# d32.net
KiCad netlist of a schematic drawn in EAGLE
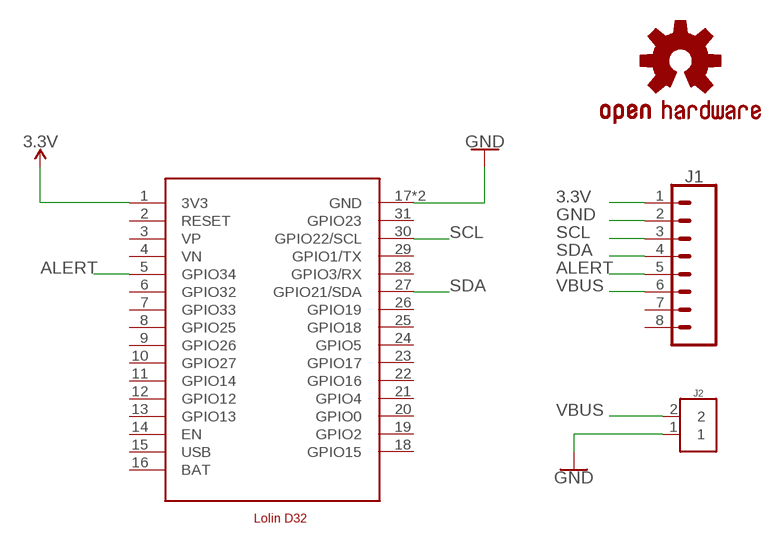
[diagram p0: schematic, sheet 1]

(export (version "E")
  (design (tool "Eeschema 10.0.6"))
  (components
    (comp (ref "J1")
      (value "CONN_08NO_SILK_FEMALE_PTH")
      (footprint "eagle-import:1X08_NO_SILK")
      (libsource (lib "eagle-import") (part "CONN_08NO_SILK_FEMALE_PTH"))
    )
    (comp (ref "J2")
      (value "282834-2")
      (footprint "eagle-import:CONN_282834-2")
      (fields (field (name "MF") "TE Connectivity"))
      (libsource (lib "eagle-import") (part "282834-2"))
    )
    (comp (ref "LOGO1")
      (value "OSHW-LOGOS")
      (footprint "eagle-import:OSHW-LOGO-S")
      (libsource (lib "eagle-import") (part "OSHW-LOGOS"))
    )
    (comp (ref "U1")
      (value "LOLIND32")
      (footprint "eagle-import:LOLIND32")
      (libsource (lib "eagle-import") (part "LOLIND32"))
    )
  )
  (nets
    (net (code "1") (name "/ALERT") (class "Default")
      (node (ref "J1") (pin "5") (pinfunction "5_5") (pintype "passive"))
      (node (ref "U1") (pin "5") (pinfunction "GPIO34_5") (pintype "input"))
    )
    (net (code "2") (name "/BAT") (class "Default")
      (node (ref "U1") (pin "16") (pinfunction "BAT_16") (pintype "power_in"))
    )
    (net (code "3") (name "/SCL") (class "Default")
      (node (ref "J1") (pin "3") (pinfunction "3_3") (pintype "passive"))
      (node (ref "U1") (pin "30") (pinfunction "GPIO22/SCL_30") (pintype "bidirectional"))
    )
    (net (code "4") (name "/SDA") (class "Default")
      (node (ref "J1") (pin "4") (pinfunction "4_4") (pintype "passive"))
      (node (ref "U1") (pin "27") (pinfunction "GPIO21/SDA_27") (pintype "bidirectional"))
    )
    (net (code "5") (name "/USB") (class "Default")
      (node (ref "U1") (pin "15") (pinfunction "USB_15") (pintype "power_in"))
    )
    (net (code "6") (name "/VBUS") (class "Default")
      (node (ref "J1") (pin "6") (pinfunction "6_6") (pintype "passive"))
      (node (ref "J2") (pin "2") (pinfunction "2_2") (pintype "passive"))
    )
    (net (code "7") (name "3.3V") (class "Default")
      (node (ref "J1") (pin "1") (pinfunction "1_1") (pintype "passive"))
      (node (ref "U1") (pin "1") (pinfunction "3V3_1") (pintype "power_in"))
    )
    (net (code "8") (name "GND") (class "Default")
      (node (ref "J1") (pin "2") (pinfunction "2_2") (pintype "passive"))
      (node (ref "J2") (pin "1") (pinfunction "1_1") (pintype "passive"))
      (node (ref "U1") (pin "17") (pinfunction "GND_17") (pintype "power_in"))
      (node (ref "U1") (pin "32") (pinfunction "GND_32") (pintype "power_in"))
    )
    (net (code "9") (name "unconnected-(J1-Pad7)") (class "Default")
      (node (ref "J1") (pin "7") (pinfunction "7_7") (pintype "passive"))
    )
    (net (code "10") (name "unconnected-(J1-Pad8)") (class "Default")
      (node (ref "J1") (pin "8") (pinfunction "8_8") (pintype "passive"))
    )
    (net (code "11") (name "unconnected-(U1-EN-Pad14)") (class "Default")
      (node (ref "U1") (pin "14") (pinfunction "EN_14") (pintype "input"))
    )
    (net (code "12") (name "unconnected-(U1-GPIO0-Pad20)") (class "Default")
      (node (ref "U1") (pin "20") (pinfunction "GPIO0_20") (pintype "bidirectional"))
    )
    (net (code "13") (name "unconnected-(U1-GPIO1{slash}TX-Pad29)") (class "Default")
      (node (ref "U1") (pin "29") (pinfunction "GPIO1/TX_29") (pintype "bidirectional"))
    )
    (net (code "14") (name "unconnected-(U1-GPIO2-Pad19)") (class "Default")
      (node (ref "U1") (pin "19") (pinfunction "GPIO2_19") (pintype "bidirectional"))
    )
    (net (code "15") (name "unconnected-(U1-GPIO3{slash}RX-Pad28)") (class "Default")
      (node (ref "U1") (pin "28") (pinfunction "GPIO3/RX_28") (pintype "bidirectional"))
    )
    (net (code "16") (name "unconnected-(U1-GPIO4-Pad21)") (class "Default")
      (node (ref "U1") (pin "21") (pinfunction "GPIO4_21") (pintype "bidirectional"))
    )
    (net (code "17") (name "unconnected-(U1-GPIO5-Pad24)") (class "Default")
      (node (ref "U1") (pin "24") (pinfunction "GPIO5_24") (pintype "bidirectional"))
    )
    (net (code "18") (name "unconnected-(U1-GPIO12-Pad12)") (class "Default")
      (node (ref "U1") (pin "12") (pinfunction "GPIO12_12") (pintype "bidirectional"))
    )
    (net (code "19") (name "unconnected-(U1-GPIO13-Pad13)") (class "Default")
      (node (ref "U1") (pin "13") (pinfunction "GPIO13_13") (pintype "bidirectional"))
    )
    (net (code "20") (name "unconnected-(U1-GPIO14-Pad11)") (class "Default")
      (node (ref "U1") (pin "11") (pinfunction "GPIO14_11") (pintype "bidirectional"))
    )
    (net (code "21") (name "unconnected-(U1-GPIO15-Pad18)") (class "Default")
      (node (ref "U1") (pin "18") (pinfunction "GPIO15_18") (pintype "bidirectional"))
    )
    (net (code "22") (name "unconnected-(U1-GPIO16-Pad22)") (class "Default")
      (node (ref "U1") (pin "22") (pinfunction "GPIO16_22") (pintype "bidirectional"))
    )
    (net (code "23") (name "unconnected-(U1-GPIO17-Pad23)") (class "Default")
      (node (ref "U1") (pin "23") (pinfunction "GPIO17_23") (pintype "bidirectional"))
    )
    (net (code "24") (name "unconnected-(U1-GPIO18-Pad25)") (class "Default")
      (node (ref "U1") (pin "25") (pinfunction "GPIO18_25") (pintype "bidirectional"))
    )
    (net (code "25") (name "unconnected-(U1-GPIO19-Pad26)") (class "Default")
      (node (ref "U1") (pin "26") (pinfunction "GPIO19_26") (pintype "bidirectional"))
    )
    (net (code "26") (name "unconnected-(U1-GPIO23-Pad31)") (class "Default")
      (node (ref "U1") (pin "31") (pinfunction "GPIO23_31") (pintype "bidirectional"))
    )
    (net (code "27") (name "unconnected-(U1-GPIO25-Pad8)") (class "Default")
      (node (ref "U1") (pin "8") (pinfunction "GPIO25_8") (pintype "bidirectional"))
    )
    (net (code "28") (name "unconnected-(U1-GPIO26-Pad9)") (class "Default")
      (node (ref "U1") (pin "9") (pinfunction "GPIO26_9") (pintype "bidirectional"))
    )
    (net (code "29") (name "unconnected-(U1-GPIO27-Pad10)") (class "Default")
      (node (ref "U1") (pin "10") (pinfunction "GPIO27_10") (pintype "bidirectional"))
    )
    (net (code "30") (name "unconnected-(U1-GPIO32-Pad6)") (class "Default")
      (node (ref "U1") (pin "6") (pinfunction "GPIO32_6") (pintype "bidirectional"))
    )
    (net (code "31") (name "unconnected-(U1-GPIO33-Pad7)") (class "Default")
      (node (ref "U1") (pin "7") (pinfunction "GPIO33_7") (pintype "bidirectional"))
    )
    (net (code "32") (name "unconnected-(U1-RESET-Pad2)") (class "Default")
      (node (ref "U1") (pin "2") (pinfunction "RESET_2") (pintype "input"))
    )
    (net (code "33") (name "unconnected-(U1-VN-Pad4)") (class "Default")
      (node (ref "U1") (pin "4") (pinfunction "VN_4") (pintype "no_connect"))
    )
    (net (code "34") (name "unconnected-(U1-VP-Pad3)") (class "Default")
      (node (ref "U1") (pin "3") (pinfunction "VP_3") (pintype "no_connect"))
    )
  )
)
